# usb_lcd.net
KiCad netlist of a schematic drawn in EAGLE
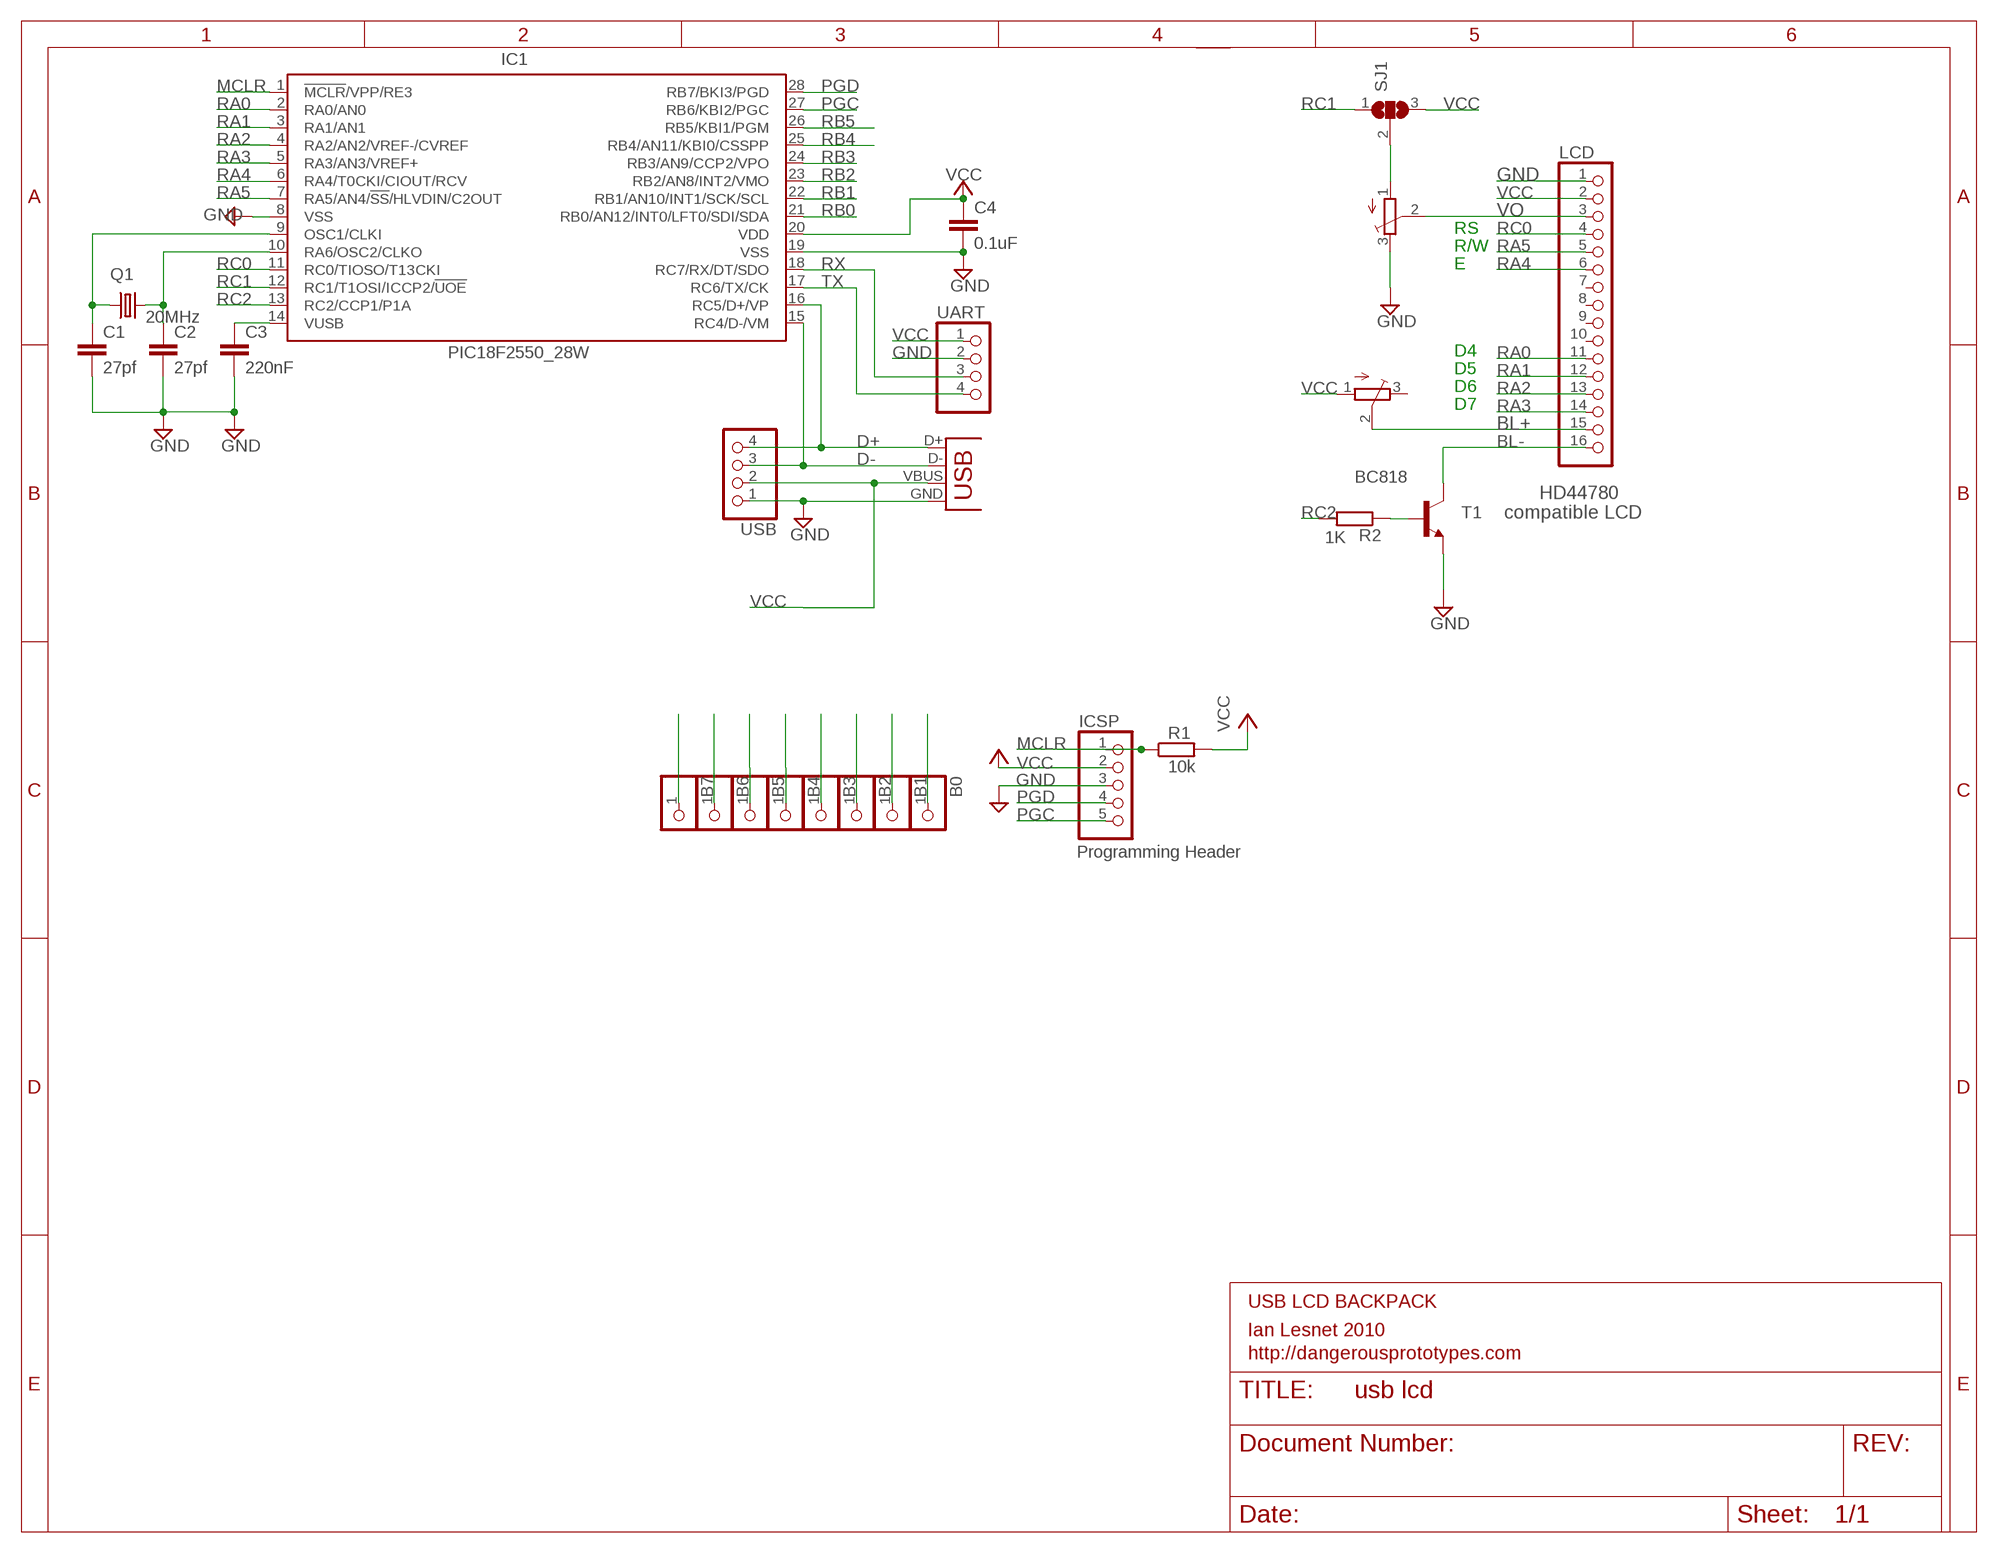
[diagram p0: schematic, sheet 1]

(export (version "E")
  (design (tool "Eeschema 10.0.6"))
  (components
    (comp (ref "B0")
      (value "PINHD-1X1")
      (footprint "eagle-import:1X01")
      (libsource (lib "eagle-import") (part "PINHD-1X1"))
    )
    (comp (ref "B1")
      (value "PINHD-1X1")
      (footprint "eagle-import:1X01")
      (libsource (lib "eagle-import") (part "PINHD-1X1"))
    )
    (comp (ref "B2")
      (value "PINHD-1X1")
      (footprint "eagle-import:1X01")
      (libsource (lib "eagle-import") (part "PINHD-1X1"))
    )
    (comp (ref "B3")
      (value "PINHD-1X1")
      (footprint "eagle-import:1X01")
      (libsource (lib "eagle-import") (part "PINHD-1X1"))
    )
    (comp (ref "B4")
      (value "PINHD-1X1")
      (footprint "eagle-import:1X01")
      (libsource (lib "eagle-import") (part "PINHD-1X1"))
    )
    (comp (ref "B5")
      (value "PINHD-1X1")
      (footprint "eagle-import:1X01")
      (libsource (lib "eagle-import") (part "PINHD-1X1"))
    )
    (comp (ref "B6")
      (value "PINHD-1X1")
      (footprint "eagle-import:1X01")
      (libsource (lib "eagle-import") (part "PINHD-1X1"))
    )
    (comp (ref "B7")
      (value "PINHD-1X1")
      (footprint "eagle-import:1X01")
      (libsource (lib "eagle-import") (part "PINHD-1X1"))
    )
    (comp (ref "C1")
      (value "27pf")
      (footprint "eagle-import:C0805")
      (libsource (lib "eagle-import") (part "C-EUC0805"))
    )
    (comp (ref "C2")
      (value "27pf")
      (footprint "eagle-import:C0805")
      (libsource (lib "eagle-import") (part "C-EUC0805"))
    )
    (comp (ref "C3")
      (value "220nF")
      (footprint "eagle-import:C0805")
      (libsource (lib "eagle-import") (part "C-EUC0805"))
    )
    (comp (ref "C4")
      (value "0.1uF")
      (footprint "eagle-import:C0805")
      (libsource (lib "eagle-import") (part "C-EUC0805"))
    )
    (comp (ref "IC1")
      (value "PIC18F2550_28W")
      (footprint "eagle-import:SO28W")
      (libsource (lib "eagle-import") (part "PIC18F2_28W550"))
    )
    (comp (ref "ICSP")
      (value "PINHD-1X5")
      (footprint "eagle-import:1X05")
      (libsource (lib "eagle-import") (part "PINHD-1X5"))
    )
    (comp (ref "J1")
      (value "USBSMD")
      (footprint "eagle-import:USB-MINIB")
      (libsource (lib "eagle-import") (part "USBSMD"))
    )
    (comp (ref "LCD")
      (value "PINHD-1X16")
      (footprint "eagle-import:1X16")
      (libsource (lib "eagle-import") (part "PINHD-1X16"))
    )
    (comp (ref "Q1")
      (value "20MHz")
      (footprint "eagle-import:HC49UP")
      (libsource (lib "eagle-import") (part "CRYSTALHC49UP"))
    )
    (comp (ref "R1")
      (value "10k")
      (footprint "eagle-import:R0805")
      (libsource (lib "eagle-import") (part "R-EU_R0805"))
    )
    (comp (ref "R2")
      (value "1K")
      (footprint "eagle-import:M0805")
      (libsource (lib "eagle-import") (part "R-EU_M0805"))
    )
    (comp (ref "SJ1")
      (value "SJ2W")
      (footprint "eagle-import:SJ_2")
      (libsource (lib "eagle-import") (part "SJ2W"))
    )
    (comp (ref "T1")
      (value "BC818")
      (footprint "eagle-import:SOT23-BEC")
      (libsource (lib "eagle-import") (part "NPNSOT23BEC"))
    )
    (comp (ref "U$3")
      (value "3MM_TRIMPOT")
      (footprint "eagle-import:3MM_TRIMPOT")
      (libsource (lib "eagle-import") (part "3MM_TRIMPOT"))
    )
    (comp (ref "U$4")
      (value "3MM_TRIMPOT")
      (footprint "eagle-import:3MM_TRIMPOT")
      (libsource (lib "eagle-import") (part "3MM_TRIMPOT"))
    )
    (comp (ref "UART")
      (value "PINHD-1X4")
      (footprint "eagle-import:1X04")
      (libsource (lib "eagle-import") (part "PINHD-1X4"))
    )
    (comp (ref "USB")
      (value "PINHD-1X4")
      (footprint "eagle-import:1X04")
      (libsource (lib "eagle-import") (part "PINHD-1X4"))
    )
  )
  (nets
    (net (code "1") (name "/BL+") (class "Default")
      (node (ref "LCD") (pin "15") (pinfunction "15_15") (pintype "passive"))
      (node (ref "U$4") (pin "2") (pinfunction "S_2") (pintype "passive"))
    )
    (net (code "2") (name "/BL-") (class "Default")
      (node (ref "LCD") (pin "16") (pinfunction "16_16") (pintype "passive"))
      (node (ref "T1") (pin "C") (pinfunction "C_C") (pintype "passive"))
    )
    (net (code "3") (name "/D+") (class "Default")
      (node (ref "IC1") (pin "16") (pinfunction "RC5/D+/VP_16") (pintype "bidirectional"))
      (node (ref "J1") (pin "D+") (pinfunction "D+_D+") (pintype "bidirectional"))
      (node (ref "USB") (pin "4") (pinfunction "4_4") (pintype "passive"))
    )
    (net (code "4") (name "/D-") (class "Default")
      (node (ref "IC1") (pin "15") (pinfunction "RC4/D-/VM_15") (pintype "bidirectional"))
      (node (ref "J1") (pin "D-") (pinfunction "D-_D-") (pintype "bidirectional"))
      (node (ref "USB") (pin "3") (pinfunction "3_3") (pintype "passive"))
    )
    (net (code "5") (name "/MCLR") (class "Default")
      (node (ref "IC1") (pin "1") (pinfunction "~{MCLR}/VPP/RE3_1") (pintype "input"))
      (node (ref "ICSP") (pin "1") (pinfunction "1_1") (pintype "passive"))
      (node (ref "R1") (pin "1") (pinfunction "1_1") (pintype "passive"))
    )
    (net (code "6") (name "/PGC") (class "Default")
      (node (ref "B6") (pin "1") (pinfunction "1_1") (pintype "passive"))
      (node (ref "IC1") (pin "27") (pinfunction "RB6/KBI2/PGC_27") (pintype "bidirectional"))
      (node (ref "ICSP") (pin "5") (pinfunction "5_5") (pintype "passive"))
    )
    (net (code "7") (name "/PGD") (class "Default")
      (node (ref "B7") (pin "1") (pinfunction "1_1") (pintype "passive"))
      (node (ref "IC1") (pin "28") (pinfunction "RB7/BKI3/PGD_28") (pintype "bidirectional"))
      (node (ref "ICSP") (pin "4") (pinfunction "4_4") (pintype "passive"))
    )
    (net (code "8") (name "/RA0") (class "Default")
      (node (ref "IC1") (pin "2") (pinfunction "RA0/AN0_2") (pintype "bidirectional"))
      (node (ref "LCD") (pin "11") (pinfunction "11_11") (pintype "passive"))
    )
    (net (code "9") (name "/RA1") (class "Default")
      (node (ref "IC1") (pin "3") (pinfunction "RA1/AN1_3") (pintype "bidirectional"))
      (node (ref "LCD") (pin "12") (pinfunction "12_12") (pintype "passive"))
    )
    (net (code "10") (name "/RA2") (class "Default")
      (node (ref "IC1") (pin "4") (pinfunction "RA2/AN2/VREF-/CVREF_4") (pintype "bidirectional"))
      (node (ref "LCD") (pin "13") (pinfunction "13_13") (pintype "passive"))
    )
    (net (code "11") (name "/RA3") (class "Default")
      (node (ref "IC1") (pin "5") (pinfunction "RA3/AN3/VREF+_5") (pintype "bidirectional"))
      (node (ref "LCD") (pin "14") (pinfunction "14_14") (pintype "passive"))
    )
    (net (code "12") (name "/RA4") (class "Default")
      (node (ref "IC1") (pin "6") (pinfunction "RA4/T0CKI/CIOUT/RCV_6") (pintype "bidirectional"))
      (node (ref "LCD") (pin "6") (pinfunction "6_6") (pintype "passive"))
    )
    (net (code "13") (name "/RA5") (class "Default")
      (node (ref "IC1") (pin "7") (pinfunction "RA5/AN4/~{SS}/HLVDIN/C2OUT_7") (pintype "bidirectional"))
      (node (ref "LCD") (pin "5") (pinfunction "5_5") (pintype "passive"))
    )
    (net (code "14") (name "/RB0") (class "Default")
      (node (ref "B0") (pin "1") (pinfunction "1_1") (pintype "passive"))
      (node (ref "IC1") (pin "21") (pinfunction "RB0/AN12/INT0/LFT0/SDI/SDA_21") (pintype "bidirectional"))
    )
    (net (code "15") (name "/RB1") (class "Default")
      (node (ref "B1") (pin "1") (pinfunction "1_1") (pintype "passive"))
      (node (ref "IC1") (pin "22") (pinfunction "RB1/AN10/INT1/SCK/SCL_22") (pintype "bidirectional"))
    )
    (net (code "16") (name "/RB2") (class "Default")
      (node (ref "B2") (pin "1") (pinfunction "1_1") (pintype "passive"))
      (node (ref "IC1") (pin "23") (pinfunction "RB2/AN8/INT2/VMO_23") (pintype "bidirectional"))
    )
    (net (code "17") (name "/RB3") (class "Default")
      (node (ref "B3") (pin "1") (pinfunction "1_1") (pintype "passive"))
      (node (ref "IC1") (pin "24") (pinfunction "RB3/AN9/CCP2/VPO_24") (pintype "bidirectional"))
    )
    (net (code "18") (name "/RB4") (class "Default")
      (node (ref "B4") (pin "1") (pinfunction "1_1") (pintype "passive"))
      (node (ref "IC1") (pin "25") (pinfunction "RB4/AN11/KBI0/CSSPP_25") (pintype "bidirectional"))
    )
    (net (code "19") (name "/RB5") (class "Default")
      (node (ref "B5") (pin "1") (pinfunction "1_1") (pintype "passive"))
      (node (ref "IC1") (pin "26") (pinfunction "RB5/KBI1/PGM_26") (pintype "bidirectional"))
    )
    (net (code "20") (name "/RC0") (class "Default")
      (node (ref "IC1") (pin "11") (pinfunction "RC0/TIOSO/T13CKI_11") (pintype "bidirectional"))
      (node (ref "LCD") (pin "4") (pinfunction "4_4") (pintype "passive"))
    )
    (net (code "21") (name "/RC1") (class "Default")
      (node (ref "IC1") (pin "12") (pinfunction "RC1/T1OSI/ICCP2/~{UOE}_12") (pintype "bidirectional"))
      (node (ref "SJ1") (pin "1") (pinfunction "1_1") (pintype "passive"))
    )
    (net (code "22") (name "/RC2") (class "Default")
      (node (ref "IC1") (pin "13") (pinfunction "RC2/CCP1/P1A_13") (pintype "bidirectional"))
      (node (ref "R2") (pin "2") (pinfunction "2_2") (pintype "passive"))
    )
    (net (code "23") (name "/RX") (class "Default")
      (node (ref "IC1") (pin "18") (pinfunction "RC7/RX/DT/SDO_18") (pintype "bidirectional"))
      (node (ref "UART") (pin "3") (pinfunction "3_3") (pintype "passive"))
    )
    (net (code "24") (name "/TX") (class "Default")
      (node (ref "IC1") (pin "17") (pinfunction "RC6/TX/CK_17") (pintype "bidirectional"))
      (node (ref "UART") (pin "4") (pinfunction "4_4") (pintype "passive"))
    )
    (net (code "25") (name "/VO") (class "Default")
      (node (ref "LCD") (pin "3") (pinfunction "3_3") (pintype "passive"))
      (node (ref "U$3") (pin "2") (pinfunction "S_2") (pintype "passive"))
    )
    (net (code "26") (name "GND") (class "Default")
      (node (ref "C1") (pin "2") (pinfunction "2_2") (pintype "passive"))
      (node (ref "C2") (pin "2") (pinfunction "2_2") (pintype "passive"))
      (node (ref "C3") (pin "2") (pinfunction "2_2") (pintype "passive"))
      (node (ref "C4") (pin "2") (pinfunction "2_2") (pintype "passive"))
      (node (ref "IC1") (pin "19") (pinfunction "VSS_19") (pintype "power_in"))
      (node (ref "IC1") (pin "8") (pinfunction "VSS_8") (pintype "power_in"))
      (node (ref "ICSP") (pin "3") (pinfunction "3_3") (pintype "passive"))
      (node (ref "J1") (pin "GND") (pinfunction "GND_GND") (pintype "bidirectional"))
      (node (ref "LCD") (pin "1") (pinfunction "1_1") (pintype "passive"))
      (node (ref "T1") (pin "E") (pinfunction "E_E") (pintype "passive"))
      (node (ref "U$3") (pin "3") (pinfunction "E_3") (pintype "passive"))
      (node (ref "UART") (pin "2") (pinfunction "2_2") (pintype "passive"))
      (node (ref "USB") (pin "1") (pinfunction "1_1") (pintype "passive"))
    )
    (net (code "27") (name "Net-(IC1-OSC1{slash}CLKI)") (class "Default")
      (node (ref "C1") (pin "1") (pinfunction "1_1") (pintype "passive"))
      (node (ref "IC1") (pin "9") (pinfunction "OSC1/CLKI_9") (pintype "input"))
      (node (ref "Q1") (pin "1") (pinfunction "1_1") (pintype "passive"))
    )
    (net (code "28") (name "Net-(IC1-RA6{slash}OSC2{slash}CLKO)") (class "Default")
      (node (ref "C2") (pin "1") (pinfunction "1_1") (pintype "passive"))
      (node (ref "IC1") (pin "10") (pinfunction "RA6/OSC2/CLKO_10") (pintype "output"))
      (node (ref "Q1") (pin "2") (pinfunction "2_2") (pintype "passive"))
    )
    (net (code "29") (name "Net-(IC1-VUSB)") (class "Default")
      (node (ref "C3") (pin "1") (pinfunction "1_1") (pintype "passive"))
      (node (ref "IC1") (pin "14") (pinfunction "VUSB_14") (pintype "bidirectional"))
    )
    (net (code "30") (name "Net-(R2-Pad1)") (class "Default")
      (node (ref "R2") (pin "1") (pinfunction "1_1") (pintype "passive"))
      (node (ref "T1") (pin "B") (pinfunction "B_B") (pintype "passive"))
    )
    (net (code "31") (name "Net-(U$3-A)") (class "Default")
      (node (ref "SJ1") (pin "2") (pinfunction "2_2") (pintype "passive"))
      (node (ref "U$3") (pin "1") (pinfunction "A_1") (pintype "passive"))
    )
    (net (code "32") (name "VCC") (class "Default")
      (node (ref "C4") (pin "1") (pinfunction "1_1") (pintype "passive"))
      (node (ref "IC1") (pin "20") (pinfunction "VDD_20") (pintype "power_in"))
      (node (ref "ICSP") (pin "2") (pinfunction "2_2") (pintype "passive"))
      (node (ref "J1") (pin "VBUS") (pinfunction "VBUS_VBUS") (pintype "bidirectional"))
      (node (ref "LCD") (pin "2") (pinfunction "2_2") (pintype "passive"))
      (node (ref "R1") (pin "2") (pinfunction "2_2") (pintype "passive"))
      (node (ref "SJ1") (pin "3") (pinfunction "3_3") (pintype "passive"))
      (node (ref "U$4") (pin "1") (pinfunction "A_1") (pintype "passive"))
      (node (ref "UART") (pin "1") (pinfunction "1_1") (pintype "passive"))
      (node (ref "USB") (pin "2") (pinfunction "2_2") (pintype "passive"))
    )
    (net (code "33") (name "unconnected-(LCD-Pad7)") (class "Default")
      (node (ref "LCD") (pin "7") (pinfunction "7_7") (pintype "passive"))
    )
    (net (code "34") (name "unconnected-(LCD-Pad8)") (class "Default")
      (node (ref "LCD") (pin "8") (pinfunction "8_8") (pintype "passive"))
    )
    (net (code "35") (name "unconnected-(LCD-Pad9)") (class "Default")
      (node (ref "LCD") (pin "9") (pinfunction "9_9") (pintype "passive"))
    )
    (net (code "36") (name "unconnected-(LCD-Pad10)") (class "Default")
      (node (ref "LCD") (pin "10") (pinfunction "10_10") (pintype "passive"))
    )
    (net (code "37") (name "unconnected-(U$4-E-Pad3)") (class "Default")
      (node (ref "U$4") (pin "3") (pinfunction "E_3") (pintype "passive"))
    )
  )
)
